# boost.net
KiCad netlist of a schematic drawn in EAGLE
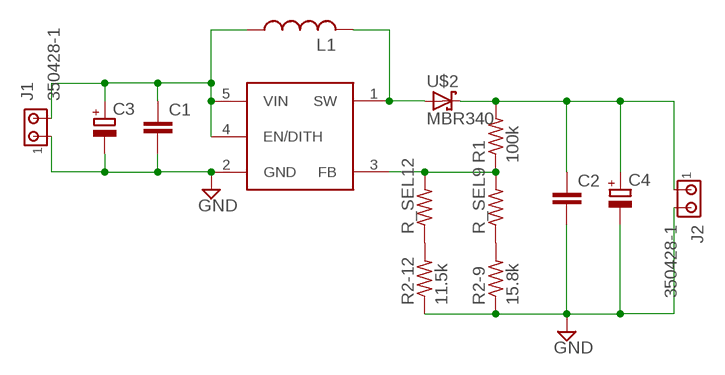
[diagram p0: schematic, sheet 1]

(export (version "E")
  (design (tool "Eeschema 10.0.6"))
  (components
    (comp (ref "C1")
      (value "C-EUC3216")
      (footprint "eagle-import:C3216")
      (libsource (lib "eagle-import") (part "C-EUC3216"))
    )
    (comp (ref "C2")
      (value "C-EUC3216")
      (footprint "eagle-import:C3216")
      (libsource (lib "eagle-import") (part "C-EUC3216"))
    )
    (comp (ref "C3")
      (value "CPOL-EUE1.8-4")
      (footprint "eagle-import:E1,8-4")
      (libsource (lib "eagle-import") (part "CPOL-EUE1.8-4"))
    )
    (comp (ref "C4")
      (value "CPOL-EUE1.8-4")
      (footprint "eagle-import:E1,8-4")
      (libsource (lib "eagle-import") (part "CPOL-EUE1.8-4"))
    )
    (comp (ref "J1")
      (value "350428-1")
      (footprint "eagle-import:350428-1")
      (libsource (lib "eagle-import") (part "350428-1"))
    )
    (comp (ref "J2")
      (value "350428-1")
      (footprint "eagle-import:350428-1")
      (libsource (lib "eagle-import") (part "350428-1"))
    )
    (comp (ref "L1")
      (value "L-US6000-XXX-RC")
      (footprint "eagle-import:6000-XXXX-RC")
      (libsource (lib "eagle-import") (part "L-US6000-XXX-RC"))
    )
    (comp (ref "R1")
      (value "100k")
      (footprint "eagle-import:M0805")
      (libsource (lib "eagle-import") (part "R-US_M0805"))
    )
    (comp (ref "R2-9")
      (value "15.8k")
      (footprint "eagle-import:M0805")
      (libsource (lib "eagle-import") (part "R-US_M0805"))
    )
    (comp (ref "R2-12")
      (value "11.5k")
      (footprint "eagle-import:M0805")
      (libsource (lib "eagle-import") (part "R-US_M0805"))
    )
    (comp (ref "R_SEL9")
      (value "R-US_R0402")
      (footprint "eagle-import:R0402")
      (libsource (lib "eagle-import") (part "R-US_R0402"))
    )
    (comp (ref "R_SEL12")
      (value "R-US_R0402")
      (footprint "eagle-import:R0402")
      (libsource (lib "eagle-import") (part "R-US_R0402"))
    )
    (comp (ref "U$1")
      (value "MIC2250-2YD5")
      (footprint "eagle-import:SOT23-5")
      (libsource (lib "eagle-import") (part "MIC2250-2YD5"))
    )
    (comp (ref "U$2")
      (value "MBR340")
      (footprint "eagle-import:MBR340-V")
      (libsource (lib "eagle-import") (part "MBR340"))
    )
  )
  (nets
    (net (code "1") (name "GND") (class "Default")
      (node (ref "C1") (pin "2") (pinfunction "2_2") (pintype "passive"))
      (node (ref "C2") (pin "2") (pinfunction "2_2") (pintype "passive"))
      (node (ref "C3") (pin "-") (pinfunction "-_-") (pintype "passive"))
      (node (ref "C4") (pin "-") (pinfunction "-_-") (pintype "passive"))
      (node (ref "J1") (pin "1") (pinfunction "1_1") (pintype "passive"))
      (node (ref "J2") (pin "2") (pinfunction "2_2") (pintype "passive"))
      (node (ref "R2-12") (pin "1") (pinfunction "1_1") (pintype "passive"))
      (node (ref "R2-9") (pin "1") (pinfunction "1_1") (pintype "passive"))
      (node (ref "U$1") (pin "2") (pinfunction "GND_2") (pintype "bidirectional"))
    )
    (net (code "2") (name "Net-(R2-9-Pad2)") (class "Default")
      (node (ref "R2-9") (pin "2") (pinfunction "2_2") (pintype "passive"))
      (node (ref "R_SEL9") (pin "1") (pinfunction "1_1") (pintype "passive"))
    )
    (net (code "3") (name "Net-(R2-12-Pad2)") (class "Default")
      (node (ref "R2-12") (pin "2") (pinfunction "2_2") (pintype "passive"))
      (node (ref "R_SEL12") (pin "1") (pinfunction "1_1") (pintype "passive"))
    )
    (net (code "4") (name "Net-(U$1-EN{slash}DITH)") (class "Default")
      (node (ref "C1") (pin "1") (pinfunction "1_1") (pintype "passive"))
      (node (ref "C3") (pin "+") (pinfunction "+_+") (pintype "passive"))
      (node (ref "J1") (pin "2") (pinfunction "2_2") (pintype "passive"))
      (node (ref "L1") (pin "1") (pinfunction "1_1") (pintype "passive"))
      (node (ref "U$1") (pin "4") (pinfunction "EN/DITH_4") (pintype "bidirectional"))
      (node (ref "U$1") (pin "5") (pinfunction "VIN_5") (pintype "bidirectional"))
    )
    (net (code "5") (name "Net-(U$1-FB)") (class "Default")
      (node (ref "R1") (pin "1") (pinfunction "1_1") (pintype "passive"))
      (node (ref "R_SEL12") (pin "2") (pinfunction "2_2") (pintype "passive"))
      (node (ref "R_SEL9") (pin "2") (pinfunction "2_2") (pintype "passive"))
      (node (ref "U$1") (pin "3") (pinfunction "FB_3") (pintype "bidirectional"))
    )
    (net (code "6") (name "Net-(U$1-SW)") (class "Default")
      (node (ref "L1") (pin "2") (pinfunction "2_2") (pintype "passive"))
      (node (ref "U$1") (pin "1") (pinfunction "SW_1") (pintype "bidirectional"))
      (node (ref "U$2") (pin "P$1") (pinfunction "A_P$1") (pintype "passive"))
    )
    (net (code "7") (name "Net-(U$2-C)") (class "Default")
      (node (ref "C2") (pin "1") (pinfunction "1_1") (pintype "passive"))
      (node (ref "C4") (pin "+") (pinfunction "+_+") (pintype "passive"))
      (node (ref "J2") (pin "1") (pinfunction "1_1") (pintype "passive"))
      (node (ref "R1") (pin "2") (pinfunction "2_2") (pintype "passive"))
      (node (ref "U$2") (pin "P$2") (pinfunction "C_P$2") (pintype "passive"))
    )
  )
)
